# klaw2bcd.net
KiCad netlist of a schematic drawn in EAGLE
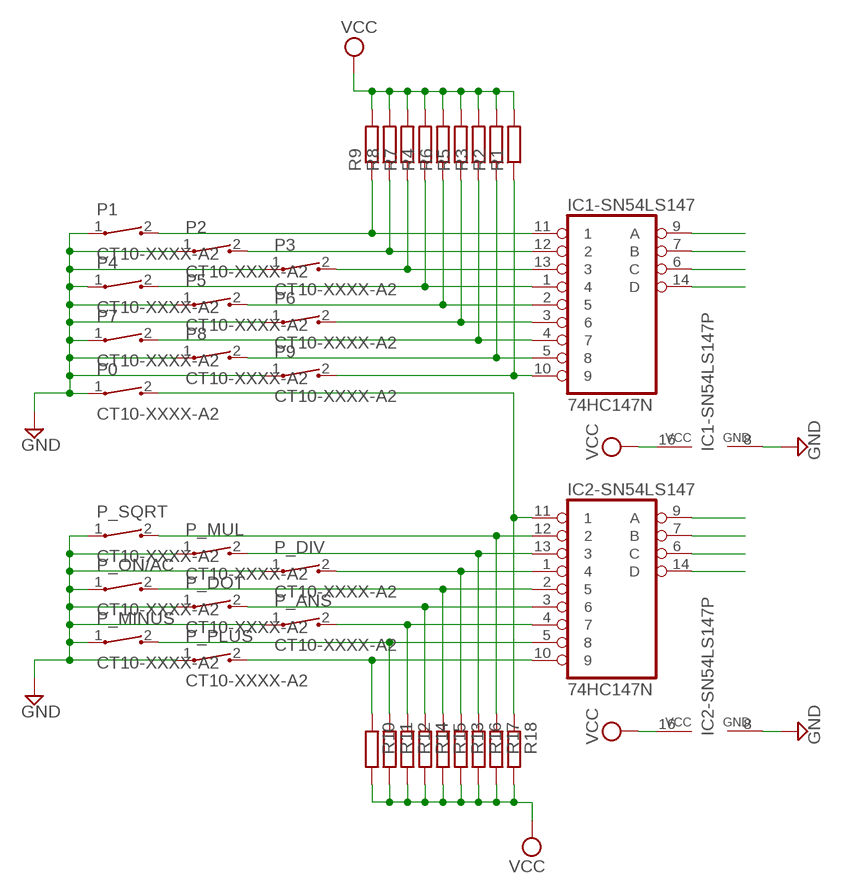
[diagram p0: schematic, sheet 1]

(export (version "E")
  (design (tool "Eeschema 10.0.6"))
  (components
    (comp (ref "IC1-SN54LS147")
      (value "74HC147N")
      (footprint "eagle-import:DIL16")
      (libsource (lib "eagle-import") (part "74147NHC"))
    )
    (comp (ref "IC2-SN54LS147")
      (value "74HC147N")
      (footprint "eagle-import:DIL16")
      (libsource (lib "eagle-import") (part "74147NHC"))
    )
    (comp (ref "P0")
      (value "CT10-XXXX-A2")
      (footprint "eagle-import:CT10-XXXX-A2")
      (libsource (lib "eagle-import") (part "CT10-XXXX-A2"))
    )
    (comp (ref "P1")
      (value "CT10-XXXX-A2")
      (footprint "eagle-import:CT10-XXXX-A2")
      (libsource (lib "eagle-import") (part "CT10-XXXX-A2"))
    )
    (comp (ref "P2")
      (value "CT10-XXXX-A2")
      (footprint "eagle-import:CT10-XXXX-A2")
      (libsource (lib "eagle-import") (part "CT10-XXXX-A2"))
    )
    (comp (ref "P3")
      (value "CT10-XXXX-A2")
      (footprint "eagle-import:CT10-XXXX-A2")
      (libsource (lib "eagle-import") (part "CT10-XXXX-A2"))
    )
    (comp (ref "P4")
      (value "CT10-XXXX-A2")
      (footprint "eagle-import:CT10-XXXX-A2")
      (libsource (lib "eagle-import") (part "CT10-XXXX-A2"))
    )
    (comp (ref "P5")
      (value "CT10-XXXX-A2")
      (footprint "eagle-import:CT10-XXXX-A2")
      (libsource (lib "eagle-import") (part "CT10-XXXX-A2"))
    )
    (comp (ref "P6")
      (value "CT10-XXXX-A2")
      (footprint "eagle-import:CT10-XXXX-A2")
      (libsource (lib "eagle-import") (part "CT10-XXXX-A2"))
    )
    (comp (ref "P7")
      (value "CT10-XXXX-A2")
      (footprint "eagle-import:CT10-XXXX-A2")
      (libsource (lib "eagle-import") (part "CT10-XXXX-A2"))
    )
    (comp (ref "P8")
      (value "CT10-XXXX-A2")
      (footprint "eagle-import:CT10-XXXX-A2")
      (libsource (lib "eagle-import") (part "CT10-XXXX-A2"))
    )
    (comp (ref "P9")
      (value "CT10-XXXX-A2")
      (footprint "eagle-import:CT10-XXXX-A2")
      (libsource (lib "eagle-import") (part "CT10-XXXX-A2"))
    )
    (comp (ref "P_ANS")
      (value "CT10-XXXX-A2")
      (footprint "eagle-import:CT10-XXXX-A2")
      (libsource (lib "eagle-import") (part "CT10-XXXX-A2"))
    )
    (comp (ref "P_DIV")
      (value "CT10-XXXX-A2")
      (footprint "eagle-import:CT10-XXXX-A2")
      (libsource (lib "eagle-import") (part "CT10-XXXX-A2"))
    )
    (comp (ref "P_DOT")
      (value "CT10-XXXX-A2")
      (footprint "eagle-import:CT10-XXXX-A2")
      (libsource (lib "eagle-import") (part "CT10-XXXX-A2"))
    )
    (comp (ref "P_MINUS")
      (value "CT10-XXXX-A2")
      (footprint "eagle-import:CT10-XXXX-A2")
      (libsource (lib "eagle-import") (part "CT10-XXXX-A2"))
    )
    (comp (ref "P_MUL")
      (value "CT10-XXXX-A2")
      (footprint "eagle-import:CT10-XXXX-A2")
      (libsource (lib "eagle-import") (part "CT10-XXXX-A2"))
    )
    (comp (ref "P_ON/AC")
      (value "CT10-XXXX-A2")
      (footprint "eagle-import:CT10-XXXX-A2")
      (libsource (lib "eagle-import") (part "CT10-XXXX-A2"))
    )
    (comp (ref "P_PLUS")
      (value "CT10-XXXX-A2")
      (footprint "eagle-import:CT10-XXXX-A2")
      (libsource (lib "eagle-import") (part "CT10-XXXX-A2"))
    )
    (comp (ref "P_SQRT")
      (value "CT10-XXXX-A2")
      (footprint "eagle-import:CT10-XXXX-A2")
      (libsource (lib "eagle-import") (part "CT10-XXXX-A2"))
    )
    (comp (ref "R1")
      (value "R-EU_0204/5")
      (footprint "eagle-import:0204_5")
      (libsource (lib "eagle-import") (part "R-EU_0204/5"))
    )
    (comp (ref "R2")
      (value "R-EU_0204/5")
      (footprint "eagle-import:0204_5")
      (libsource (lib "eagle-import") (part "R-EU_0204/5"))
    )
    (comp (ref "R3")
      (value "R-EU_0204/5")
      (footprint "eagle-import:0204_5")
      (libsource (lib "eagle-import") (part "R-EU_0204/5"))
    )
    (comp (ref "R4")
      (value "R-EU_0204/5")
      (footprint "eagle-import:0204_5")
      (libsource (lib "eagle-import") (part "R-EU_0204/5"))
    )
    (comp (ref "R5")
      (value "R-EU_0204/5")
      (footprint "eagle-import:0204_5")
      (libsource (lib "eagle-import") (part "R-EU_0204/5"))
    )
    (comp (ref "R6")
      (value "R-EU_0204/5")
      (footprint "eagle-import:0204_5")
      (libsource (lib "eagle-import") (part "R-EU_0204/5"))
    )
    (comp (ref "R7")
      (value "R-EU_0204/5")
      (footprint "eagle-import:0204_5")
      (libsource (lib "eagle-import") (part "R-EU_0204/5"))
    )
    (comp (ref "R8")
      (value "R-EU_0204/5")
      (footprint "eagle-import:0204_5")
      (libsource (lib "eagle-import") (part "R-EU_0204/5"))
    )
    (comp (ref "R9")
      (value "R-EU_0204/5")
      (footprint "eagle-import:0204_5")
      (libsource (lib "eagle-import") (part "R-EU_0204/5"))
    )
    (comp (ref "R10")
      (value "R-EU_0204/5")
      (footprint "eagle-import:0204_5")
      (libsource (lib "eagle-import") (part "R-EU_0204/5"))
    )
    (comp (ref "R11")
      (value "R-EU_0204/5")
      (footprint "eagle-import:0204_5")
      (libsource (lib "eagle-import") (part "R-EU_0204/5"))
    )
    (comp (ref "R12")
      (value "R-EU_0204/5")
      (footprint "eagle-import:0204_5")
      (libsource (lib "eagle-import") (part "R-EU_0204/5"))
    )
    (comp (ref "R13")
      (value "R-EU_0204/5")
      (footprint "eagle-import:0204_5")
      (libsource (lib "eagle-import") (part "R-EU_0204/5"))
    )
    (comp (ref "R14")
      (value "R-EU_0204/5")
      (footprint "eagle-import:0204_5")
      (libsource (lib "eagle-import") (part "R-EU_0204/5"))
    )
    (comp (ref "R15")
      (value "R-EU_0204/5")
      (footprint "eagle-import:0204_5")
      (libsource (lib "eagle-import") (part "R-EU_0204/5"))
    )
    (comp (ref "R16")
      (value "R-EU_0204/5")
      (footprint "eagle-import:0204_5")
      (libsource (lib "eagle-import") (part "R-EU_0204/5"))
    )
    (comp (ref "R17")
      (value "R-EU_0204/5")
      (footprint "eagle-import:0204_5")
      (libsource (lib "eagle-import") (part "R-EU_0204/5"))
    )
    (comp (ref "R18")
      (value "R-EU_0204/5")
      (footprint "eagle-import:0204_5")
      (libsource (lib "eagle-import") (part "R-EU_0204/5"))
    )
  )
  (nets
    (net (code "1") (name "GND") (class "Default")
      (node (ref "IC1-SN54LS147") (pin "8") (pinfunction "GND_8") (pintype "power_in"))
      (node (ref "IC2-SN54LS147") (pin "8") (pinfunction "GND_8") (pintype "power_in"))
      (node (ref "P0") (pin "1") (pinfunction "1_1") (pintype "passive"))
      (node (ref "P1") (pin "1") (pinfunction "1_1") (pintype "passive"))
      (node (ref "P2") (pin "1") (pinfunction "1_1") (pintype "passive"))
      (node (ref "P3") (pin "1") (pinfunction "1_1") (pintype "passive"))
      (node (ref "P4") (pin "1") (pinfunction "1_1") (pintype "passive"))
      (node (ref "P5") (pin "1") (pinfunction "1_1") (pintype "passive"))
      (node (ref "P6") (pin "1") (pinfunction "1_1") (pintype "passive"))
      (node (ref "P7") (pin "1") (pinfunction "1_1") (pintype "passive"))
      (node (ref "P8") (pin "1") (pinfunction "1_1") (pintype "passive"))
      (node (ref "P9") (pin "1") (pinfunction "1_1") (pintype "passive"))
      (node (ref "P_ANS") (pin "1") (pinfunction "1_1") (pintype "passive"))
      (node (ref "P_DIV") (pin "1") (pinfunction "1_1") (pintype "passive"))
      (node (ref "P_DOT") (pin "1") (pinfunction "1_1") (pintype "passive"))
      (node (ref "P_MINUS") (pin "1") (pinfunction "1_1") (pintype "passive"))
      (node (ref "P_MUL") (pin "1") (pinfunction "1_1") (pintype "passive"))
      (node (ref "P_ON/AC") (pin "1") (pinfunction "1_1") (pintype "passive"))
      (node (ref "P_PLUS") (pin "1") (pinfunction "1_1") (pintype "passive"))
      (node (ref "P_SQRT") (pin "1") (pinfunction "1_1") (pintype "passive"))
    )
    (net (code "2") (name "Net-(IC1-SN54LS147A-1)") (class "Default")
      (node (ref "IC1-SN54LS147") (pin "11") (pinfunction "1_11") (pintype "input"))
      (node (ref "P1") (pin "2") (pinfunction "2_2") (pintype "passive"))
      (node (ref "R9") (pin "1") (pinfunction "1_1") (pintype "passive"))
    )
    (net (code "3") (name "Net-(IC1-SN54LS147A-2)") (class "Default")
      (node (ref "IC1-SN54LS147") (pin "12") (pinfunction "2_12") (pintype "input"))
      (node (ref "P2") (pin "2") (pinfunction "2_2") (pintype "passive"))
      (node (ref "R8") (pin "1") (pinfunction "1_1") (pintype "passive"))
    )
    (net (code "4") (name "Net-(IC1-SN54LS147A-3)") (class "Default")
      (node (ref "IC1-SN54LS147") (pin "13") (pinfunction "3_13") (pintype "input"))
      (node (ref "P3") (pin "2") (pinfunction "2_2") (pintype "passive"))
      (node (ref "R7") (pin "1") (pinfunction "1_1") (pintype "passive"))
    )
    (net (code "5") (name "Net-(IC1-SN54LS147A-4)") (class "Default")
      (node (ref "IC1-SN54LS147") (pin "1") (pinfunction "4_1") (pintype "input"))
      (node (ref "P4") (pin "2") (pinfunction "2_2") (pintype "passive"))
      (node (ref "R4") (pin "1") (pinfunction "1_1") (pintype "passive"))
    )
    (net (code "6") (name "Net-(IC1-SN54LS147A-5)") (class "Default")
      (node (ref "IC1-SN54LS147") (pin "2") (pinfunction "5_2") (pintype "input"))
      (node (ref "P5") (pin "2") (pinfunction "2_2") (pintype "passive"))
      (node (ref "R6") (pin "1") (pinfunction "1_1") (pintype "passive"))
    )
    (net (code "7") (name "Net-(IC1-SN54LS147A-6)") (class "Default")
      (node (ref "IC1-SN54LS147") (pin "3") (pinfunction "6_3") (pintype "input"))
      (node (ref "P6") (pin "2") (pinfunction "2_2") (pintype "passive"))
      (node (ref "R5") (pin "1") (pinfunction "1_1") (pintype "passive"))
    )
    (net (code "8") (name "Net-(IC1-SN54LS147A-7)") (class "Default")
      (node (ref "IC1-SN54LS147") (pin "4") (pinfunction "7_4") (pintype "input"))
      (node (ref "P7") (pin "2") (pinfunction "2_2") (pintype "passive"))
      (node (ref "R3") (pin "1") (pinfunction "1_1") (pintype "passive"))
    )
    (net (code "9") (name "Net-(IC1-SN54LS147A-8)") (class "Default")
      (node (ref "IC1-SN54LS147") (pin "5") (pinfunction "8_5") (pintype "input"))
      (node (ref "P8") (pin "2") (pinfunction "2_2") (pintype "passive"))
      (node (ref "R2") (pin "1") (pinfunction "1_1") (pintype "passive"))
    )
    (net (code "10") (name "Net-(IC1-SN54LS147A-9)") (class "Default")
      (node (ref "IC1-SN54LS147") (pin "10") (pinfunction "9_10") (pintype "input"))
      (node (ref "P9") (pin "2") (pinfunction "2_2") (pintype "passive"))
      (node (ref "R1") (pin "1") (pinfunction "1_1") (pintype "passive"))
    )
    (net (code "11") (name "Net-(IC2-SN54LS147A-1)") (class "Default")
      (node (ref "IC2-SN54LS147") (pin "11") (pinfunction "1_11") (pintype "input"))
      (node (ref "P0") (pin "2") (pinfunction "2_2") (pintype "passive"))
      (node (ref "R18") (pin "1") (pinfunction "1_1") (pintype "passive"))
    )
    (net (code "12") (name "Net-(IC2-SN54LS147A-2)") (class "Default")
      (node (ref "IC2-SN54LS147") (pin "12") (pinfunction "2_12") (pintype "input"))
      (node (ref "P_SQRT") (pin "2") (pinfunction "2_2") (pintype "passive"))
      (node (ref "R17") (pin "1") (pinfunction "1_1") (pintype "passive"))
    )
    (net (code "13") (name "Net-(IC2-SN54LS147A-3)") (class "Default")
      (node (ref "IC2-SN54LS147") (pin "13") (pinfunction "3_13") (pintype "input"))
      (node (ref "P_MUL") (pin "2") (pinfunction "2_2") (pintype "passive"))
      (node (ref "R16") (pin "1") (pinfunction "1_1") (pintype "passive"))
    )
    (net (code "14") (name "Net-(IC2-SN54LS147A-4)") (class "Default")
      (node (ref "IC2-SN54LS147") (pin "1") (pinfunction "4_1") (pintype "input"))
      (node (ref "P_DIV") (pin "2") (pinfunction "2_2") (pintype "passive"))
      (node (ref "R13") (pin "1") (pinfunction "1_1") (pintype "passive"))
    )
    (net (code "15") (name "Net-(IC2-SN54LS147A-5)") (class "Default")
      (node (ref "IC2-SN54LS147") (pin "2") (pinfunction "5_2") (pintype "input"))
      (node (ref "P_ON/AC") (pin "2") (pinfunction "2_2") (pintype "passive"))
      (node (ref "R15") (pin "1") (pinfunction "1_1") (pintype "passive"))
    )
    (net (code "16") (name "Net-(IC2-SN54LS147A-6)") (class "Default")
      (node (ref "IC2-SN54LS147") (pin "3") (pinfunction "6_3") (pintype "input"))
      (node (ref "P_DOT") (pin "2") (pinfunction "2_2") (pintype "passive"))
      (node (ref "R14") (pin "1") (pinfunction "1_1") (pintype "passive"))
    )
    (net (code "17") (name "Net-(IC2-SN54LS147A-7)") (class "Default")
      (node (ref "IC2-SN54LS147") (pin "4") (pinfunction "7_4") (pintype "input"))
      (node (ref "P_ANS") (pin "2") (pinfunction "2_2") (pintype "passive"))
      (node (ref "R12") (pin "1") (pinfunction "1_1") (pintype "passive"))
    )
    (net (code "18") (name "Net-(IC2-SN54LS147A-8)") (class "Default")
      (node (ref "IC2-SN54LS147") (pin "5") (pinfunction "8_5") (pintype "input"))
      (node (ref "P_MINUS") (pin "2") (pinfunction "2_2") (pintype "passive"))
      (node (ref "R11") (pin "1") (pinfunction "1_1") (pintype "passive"))
    )
    (net (code "19") (name "Net-(IC2-SN54LS147A-9)") (class "Default")
      (node (ref "IC2-SN54LS147") (pin "10") (pinfunction "9_10") (pintype "input"))
      (node (ref "P_PLUS") (pin "2") (pinfunction "2_2") (pintype "passive"))
      (node (ref "R10") (pin "1") (pinfunction "1_1") (pintype "passive"))
    )
    (net (code "20") (name "VCC") (class "Default")
      (node (ref "IC1-SN54LS147") (pin "16") (pinfunction "VCC_16") (pintype "power_in"))
      (node (ref "IC2-SN54LS147") (pin "16") (pinfunction "VCC_16") (pintype "power_in"))
      (node (ref "R1") (pin "2") (pinfunction "2_2") (pintype "passive"))
      (node (ref "R10") (pin "2") (pinfunction "2_2") (pintype "passive"))
      (node (ref "R11") (pin "2") (pinfunction "2_2") (pintype "passive"))
      (node (ref "R12") (pin "2") (pinfunction "2_2") (pintype "passive"))
      (node (ref "R13") (pin "2") (pinfunction "2_2") (pintype "passive"))
      (node (ref "R14") (pin "2") (pinfunction "2_2") (pintype "passive"))
      (node (ref "R15") (pin "2") (pinfunction "2_2") (pintype "passive"))
      (node (ref "R16") (pin "2") (pinfunction "2_2") (pintype "passive"))
      (node (ref "R17") (pin "2") (pinfunction "2_2") (pintype "passive"))
      (node (ref "R18") (pin "2") (pinfunction "2_2") (pintype "passive"))
      (node (ref "R2") (pin "2") (pinfunction "2_2") (pintype "passive"))
      (node (ref "R3") (pin "2") (pinfunction "2_2") (pintype "passive"))
      (node (ref "R4") (pin "2") (pinfunction "2_2") (pintype "passive"))
      (node (ref "R5") (pin "2") (pinfunction "2_2") (pintype "passive"))
      (node (ref "R6") (pin "2") (pinfunction "2_2") (pintype "passive"))
      (node (ref "R7") (pin "2") (pinfunction "2_2") (pintype "passive"))
      (node (ref "R8") (pin "2") (pinfunction "2_2") (pintype "passive"))
      (node (ref "R9") (pin "2") (pinfunction "2_2") (pintype "passive"))
    )
    (net (code "21") (name "unconnected-(IC1-SN54LS147A-A-Pad9)") (class "Default")
      (node (ref "IC1-SN54LS147") (pin "9") (pinfunction "A_9") (pintype "output"))
    )
    (net (code "22") (name "unconnected-(IC1-SN54LS147A-B-Pad7)") (class "Default")
      (node (ref "IC1-SN54LS147") (pin "7") (pinfunction "B_7") (pintype "output"))
    )
    (net (code "23") (name "unconnected-(IC1-SN54LS147A-C-Pad6)") (class "Default")
      (node (ref "IC1-SN54LS147") (pin "6") (pinfunction "C_6") (pintype "output"))
    )
    (net (code "24") (name "unconnected-(IC1-SN54LS147A-D-Pad14)") (class "Default")
      (node (ref "IC1-SN54LS147") (pin "14") (pinfunction "D_14") (pintype "output"))
    )
    (net (code "25") (name "unconnected-(IC2-SN54LS147A-A-Pad9)") (class "Default")
      (node (ref "IC2-SN54LS147") (pin "9") (pinfunction "A_9") (pintype "output"))
    )
    (net (code "26") (name "unconnected-(IC2-SN54LS147A-B-Pad7)") (class "Default")
      (node (ref "IC2-SN54LS147") (pin "7") (pinfunction "B_7") (pintype "output"))
    )
    (net (code "27") (name "unconnected-(IC2-SN54LS147A-C-Pad6)") (class "Default")
      (node (ref "IC2-SN54LS147") (pin "6") (pinfunction "C_6") (pintype "output"))
    )
    (net (code "28") (name "unconnected-(IC2-SN54LS147A-D-Pad14)") (class "Default")
      (node (ref "IC2-SN54LS147") (pin "14") (pinfunction "D_14") (pintype "output"))
    )
  )
)
